# 04_-_VIDEO_INPUT.net
KiCad netlist of a schematic drawn in Altium Designer
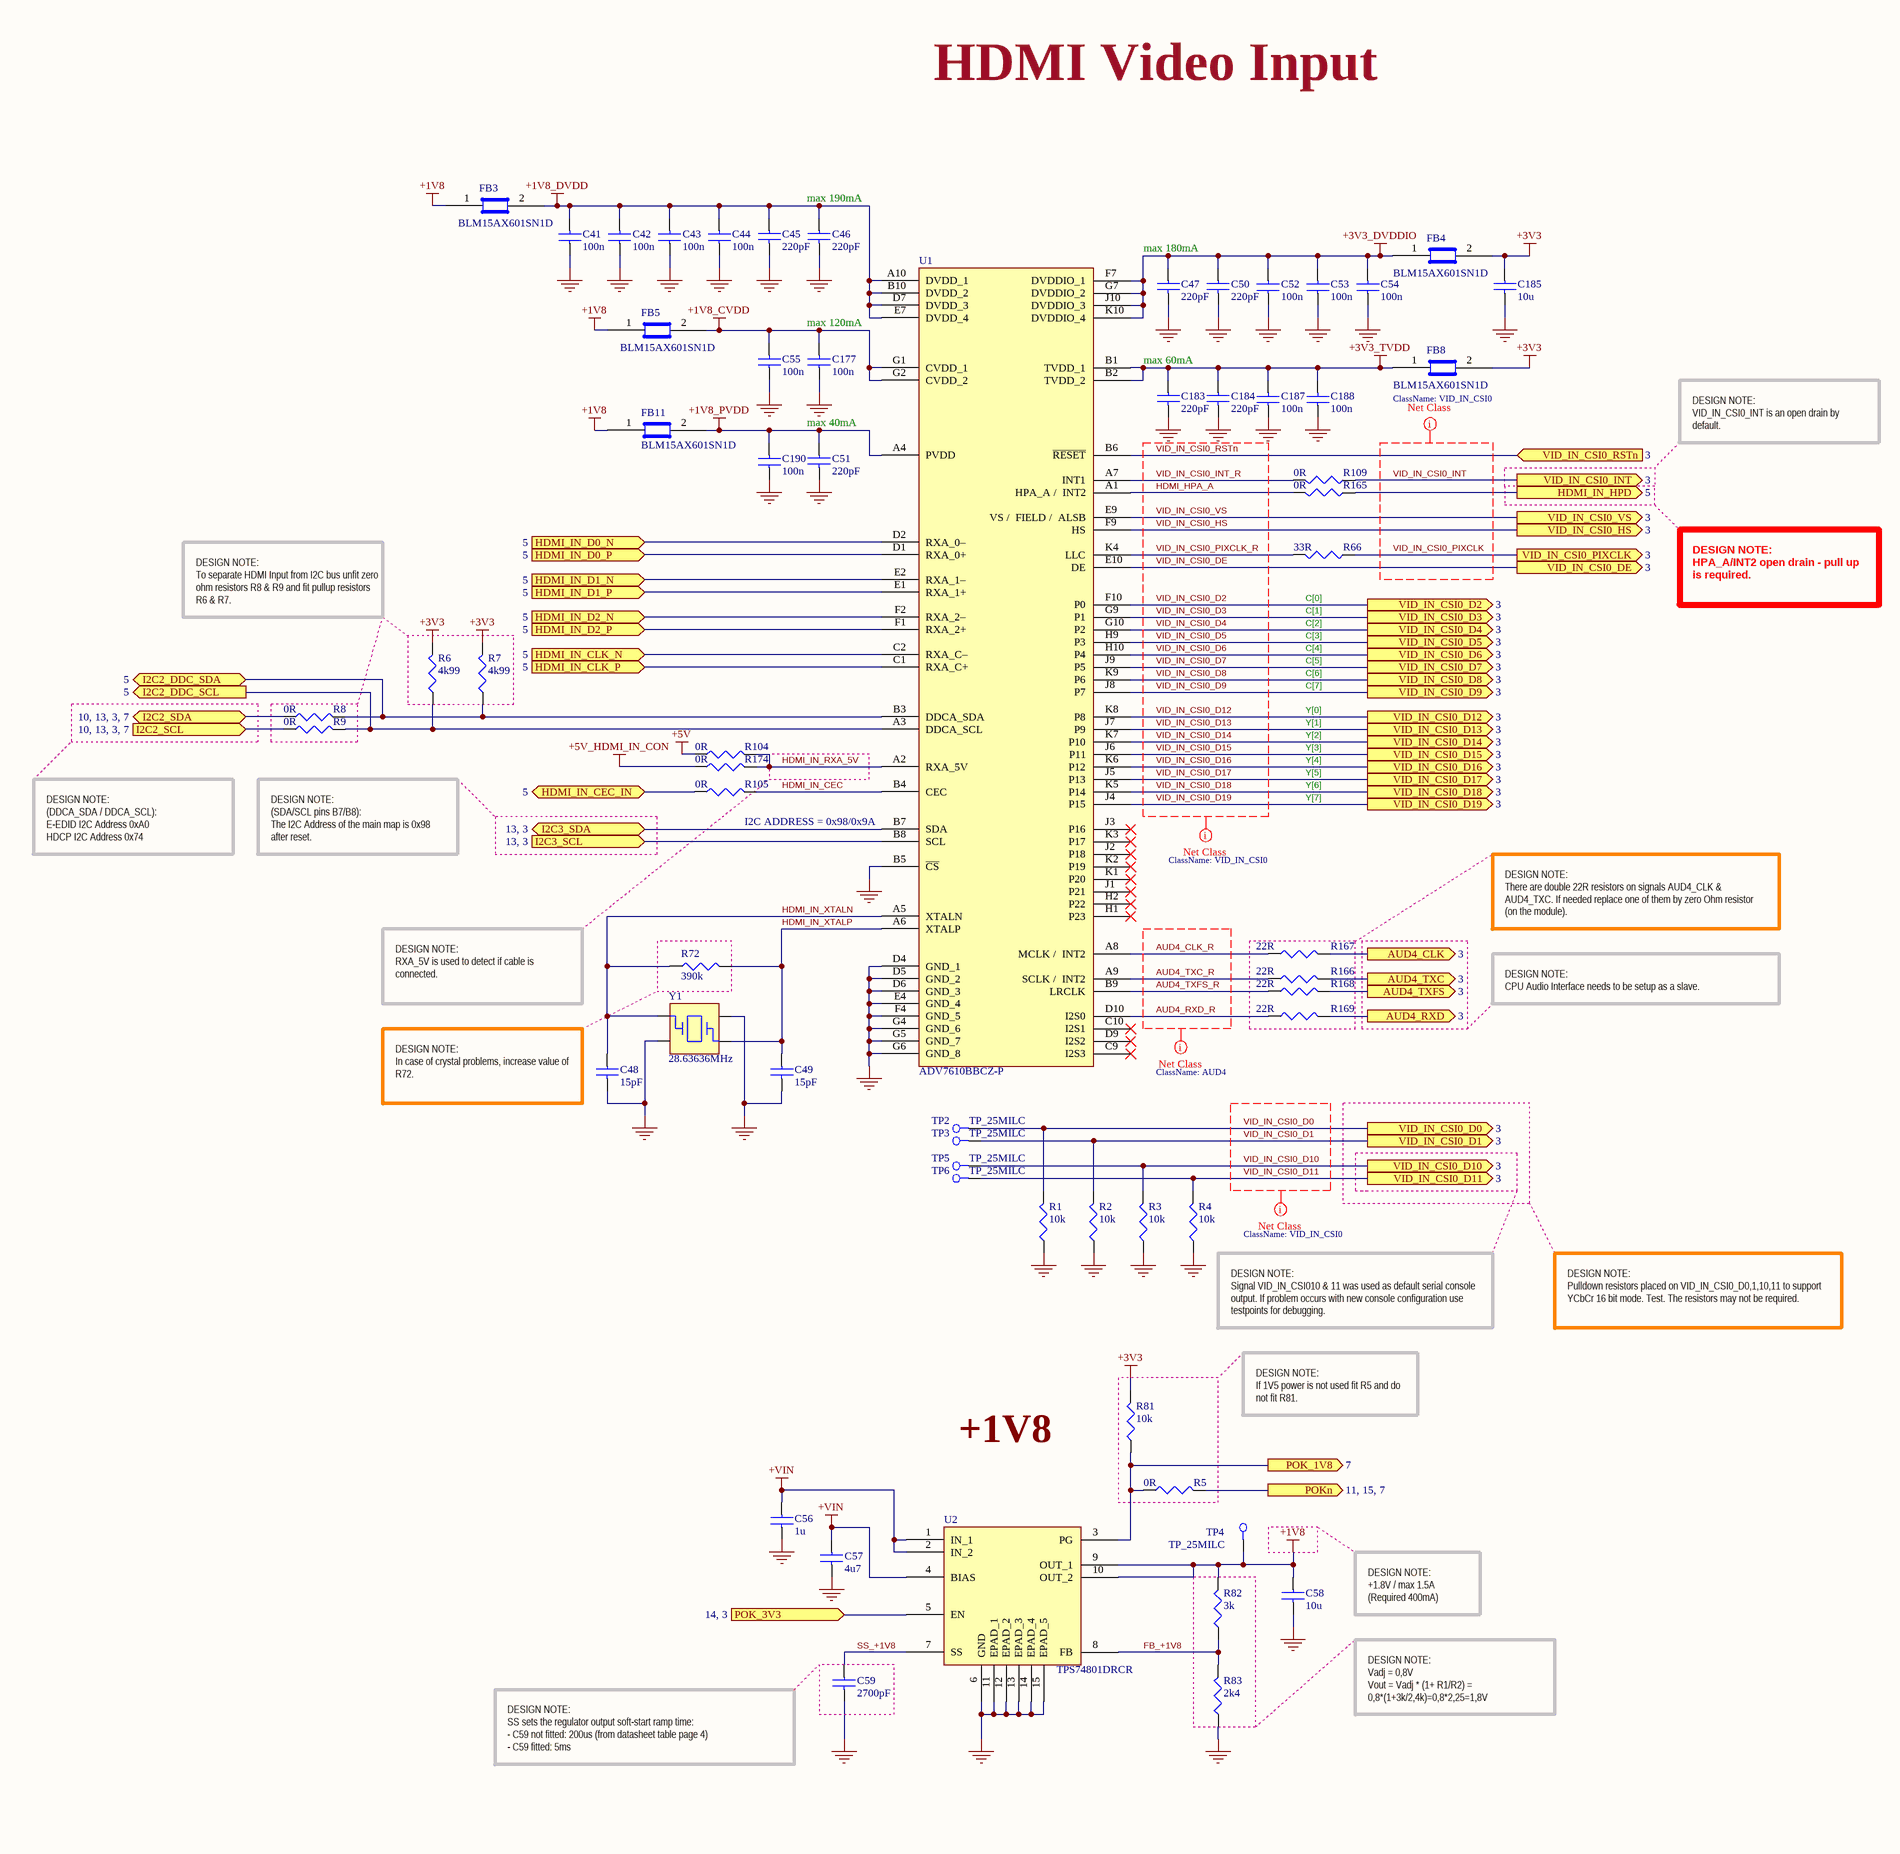
[diagram p0: [04] - VIDEO INPUT.SchDoc, left]
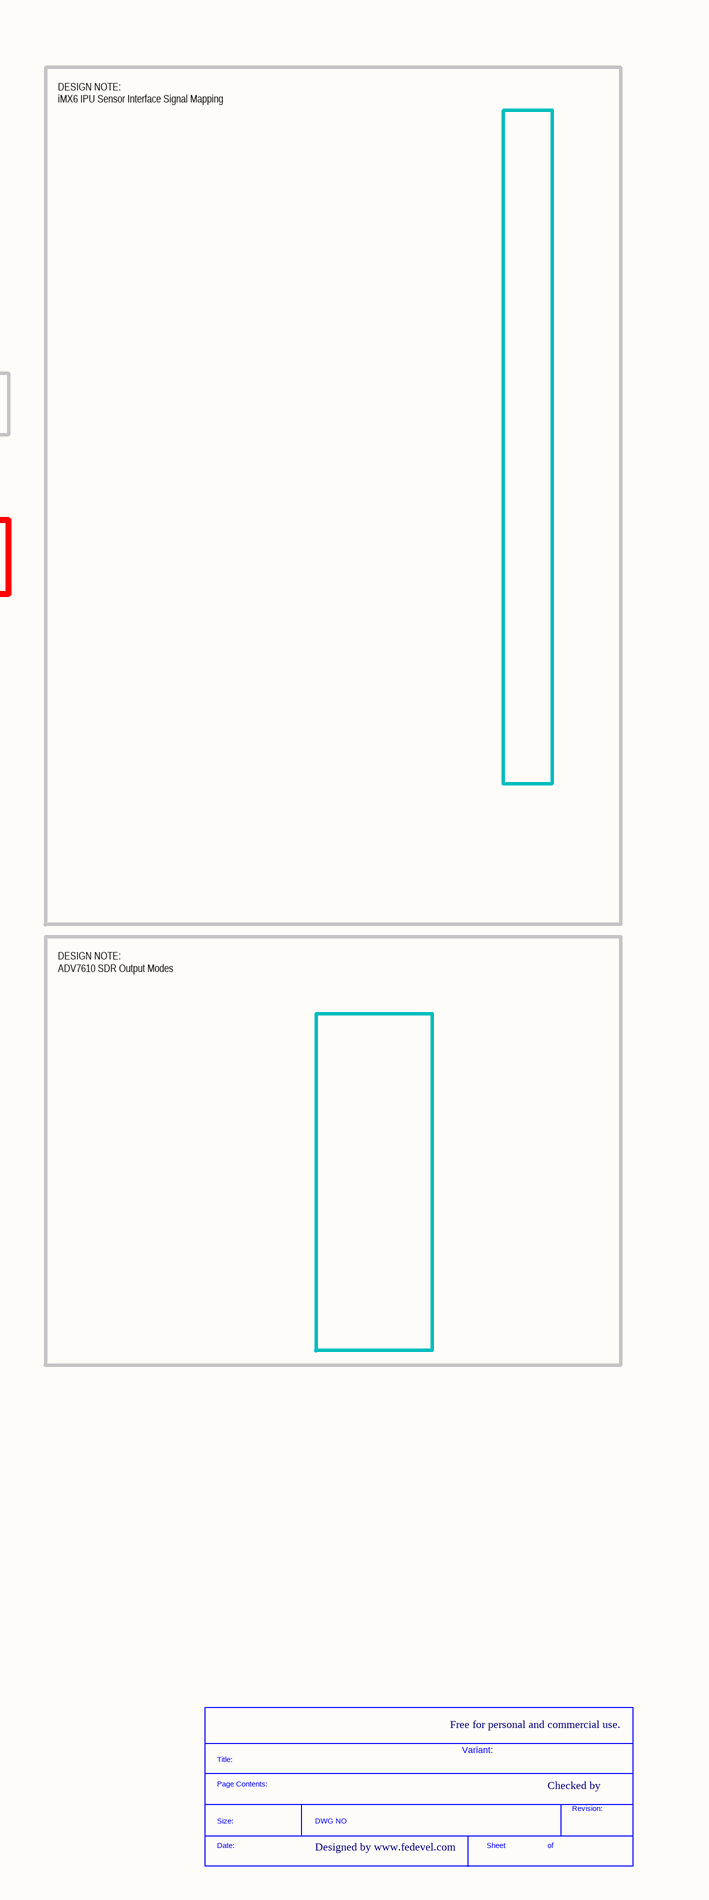
[diagram p1: [04] - VIDEO INPUT.SchDoc, right]

(export (version "E")
  (design (tool "Eeschema 10.0.6"))
  (components
    (comp (ref "C41")
      (value "100n")
      (footprint "C0402")
      (description "CAP CER .10UF 50V X5R 10% 0402")
      (fields
        (field (name "MANUFACTURER") "TDK Corporation")
        (field (name "MANUFACTURER PART NUMBER") "C1005X5R1H104K")
      )
      (libsource (lib "Integrated_Library_FEDEVEL_APR_2015") (part "C1005X5R1H104K"))
    )
    (comp (ref "C42")
      (value "100n")
      (footprint "C0402")
      (description "CAP CER .10UF 50V X5R 10% 0402")
      (fields
        (field (name "MANUFACTURER") "TDK Corporation")
        (field (name "MANUFACTURER PART NUMBER") "C1005X5R1H104K")
      )
      (libsource (lib "Integrated_Library_FEDEVEL_APR_2015") (part "C1005X5R1H104K"))
    )
    (comp (ref "C43")
      (value "100n")
      (footprint "C0402")
      (description "CAP CER .10UF 50V X5R 10% 0402")
      (fields
        (field (name "MANUFACTURER") "TDK Corporation")
        (field (name "MANUFACTURER PART NUMBER") "C1005X5R1H104K")
      )
      (libsource (lib "Integrated_Library_FEDEVEL_APR_2015") (part "C1005X5R1H104K"))
    )
    (comp (ref "C44")
      (value "100n")
      (footprint "C0402")
      (description "CAP CER .10UF 50V X5R 10% 0402")
      (fields
        (field (name "MANUFACTURER") "TDK Corporation")
        (field (name "MANUFACTURER PART NUMBER") "C1005X5R1H104K")
      )
      (libsource (lib "Integrated_Library_FEDEVEL_APR_2015") (part "C1005X5R1H104K"))
    )
    (comp (ref "C45")
      (value "220pF")
      (footprint "C0402")
      (description "CAP CER 220PF 50V X7R 10% 0402")
      (fields
        (field (name "MANUFACTURER") "TDK Corporation")
        (field (name "MANUFACTURER PART NUMBER") "C1005X7R1H221K")
      )
      (libsource (lib "Integrated_Library_FEDEVEL_APR_2015") (part "C1005X7R1H221K"))
    )
    (comp (ref "C46")
      (value "220pF")
      (footprint "C0402")
      (description "CAP CER 220PF 50V X7R 10% 0402")
      (fields
        (field (name "MANUFACTURER") "TDK Corporation")
        (field (name "MANUFACTURER PART NUMBER") "C1005X7R1H221K")
      )
      (libsource (lib "Integrated_Library_FEDEVEL_APR_2015") (part "C1005X7R1H221K"))
    )
    (comp (ref "C47")
      (value "220pF")
      (footprint "C0402")
      (description "CAP CER 220PF 50V X7R 10% 0402")
      (fields
        (field (name "MANUFACTURER") "TDK Corporation")
        (field (name "MANUFACTURER PART NUMBER") "C1005X7R1H221K")
      )
      (libsource (lib "Integrated_Library_FEDEVEL_APR_2015") (part "C1005X7R1H221K"))
    )
    (comp (ref "C48")
      (value "15pF")
      (footprint "C0402")
      (description "CAP CER 15PF 50V 5% NP0 0402")
      (fields
        (field (name "MANUFACTURER") "TDK Corporation")
        (field (name "MANUFACTURER PART NUMBER") "C1005C0G1H150J")
      )
      (libsource (lib "Integrated_Library_FEDEVEL_APR_2015") (part "C1005C0G1H150J"))
    )
    (comp (ref "C49")
      (value "15pF")
      (footprint "C0402")
      (description "CAP CER 15PF 50V 5% NP0 0402")
      (fields
        (field (name "MANUFACTURER") "TDK Corporation")
        (field (name "MANUFACTURER PART NUMBER") "C1005C0G1H150J")
      )
      (libsource (lib "Integrated_Library_FEDEVEL_APR_2015") (part "C1005C0G1H150J"))
    )
    (comp (ref "C50")
      (value "220pF")
      (footprint "C0402")
      (description "CAP CER 220PF 50V X7R 10% 0402")
      (fields
        (field (name "MANUFACTURER") "TDK Corporation")
        (field (name "MANUFACTURER PART NUMBER") "C1005X7R1H221K")
      )
      (libsource (lib "Integrated_Library_FEDEVEL_APR_2015") (part "C1005X7R1H221K"))
    )
    (comp (ref "C51")
      (value "220pF")
      (footprint "C0402")
      (description "CAP CER 220PF 50V X7R 10% 0402")
      (fields
        (field (name "MANUFACTURER") "TDK Corporation")
        (field (name "MANUFACTURER PART NUMBER") "C1005X7R1H221K")
      )
      (libsource (lib "Integrated_Library_FEDEVEL_APR_2015") (part "C1005X7R1H221K"))
    )
    (comp (ref "C52")
      (value "100n")
      (footprint "C0402")
      (description "CAP CER .10UF 50V X5R 10% 0402")
      (fields
        (field (name "MANUFACTURER") "TDK Corporation")
        (field (name "MANUFACTURER PART NUMBER") "C1005X5R1H104K")
      )
      (libsource (lib "Integrated_Library_FEDEVEL_APR_2015") (part "C1005X5R1H104K"))
    )
    (comp (ref "C53")
      (value "100n")
      (footprint "C0402")
      (description "CAP CER .10UF 50V X5R 10% 0402")
      (fields
        (field (name "MANUFACTURER") "TDK Corporation")
        (field (name "MANUFACTURER PART NUMBER") "C1005X5R1H104K")
      )
      (libsource (lib "Integrated_Library_FEDEVEL_APR_2015") (part "C1005X5R1H104K"))
    )
    (comp (ref "C54")
      (value "100n")
      (footprint "C0402")
      (description "CAP CER .10UF 50V X5R 10% 0402")
      (fields
        (field (name "MANUFACTURER") "TDK Corporation")
        (field (name "MANUFACTURER PART NUMBER") "C1005X5R1H104K")
      )
      (libsource (lib "Integrated_Library_FEDEVEL_APR_2015") (part "C1005X5R1H104K"))
    )
    (comp (ref "C55")
      (value "100n")
      (footprint "C0402")
      (description "CAP CER .10UF 50V X5R 10% 0402")
      (fields
        (field (name "MANUFACTURER") "TDK Corporation")
        (field (name "MANUFACTURER PART NUMBER") "C1005X5R1H104K")
      )
      (libsource (lib "Integrated_Library_FEDEVEL_APR_2015") (part "C1005X5R1H104K"))
    )
    (comp (ref "C56")
      (value "1u")
      (footprint "C0402")
      (description "CAP CER 1.0UF 16V X5R 0402")
      (fields
        (field (name "MANUFACTURER") "TDK Corporation")
        (field (name "MANUFACTURER PART NUMBER") "C1005X5R1C105K")
      )
      (libsource (lib "Integrated_Library_FEDEVEL_APR_2015") (part "C1005X5R1C105K"))
    )
    (comp (ref "C57")
      (value "4u7")
      (footprint "C0402")
      (description "CAP CER 4.7UF 10V 20% X5R 0402")
      (fields
        (field (name "MANUFACTURER") "TDK Corporation")
        (field (name "MANUFACTURER PART NUMBER") "C1005X5R1A475M")
      )
      (libsource (lib "Integrated_Library_FEDEVEL_APR_2015") (part "C1005X5R1A475M"))
    )
    (comp (ref "C58")
      (value "10u")
      (footprint "C0603")
      (description "CAP CER 10UF 6.3V X5R 20% 0603")
      (fields
        (field (name "MANUFACTURER") "TDK Corporation")
        (field (name "MANUFACTURER PART NUMBER") "C1608X5R0J106M")
      )
      (libsource (lib "Integrated_Library_FEDEVEL_APR_2015") (part "C1608X5R0J106M"))
    )
    (comp (ref "C59")
      (value "2700pF")
      (footprint "C0402")
      (description "CAP CER 2700PF 50V 10% X7R 0402")
      (fields
        (field (name "MANUFACTURER") "Murata Electronics North America")
        (field (name "MANUFACTURER PART NUMBER") "GRM155R71H272KA01D")
      )
      (libsource (lib "Integrated_Library_FEDEVEL_APR_2015") (part "GRM155R71H272KA01D"))
    )
    (comp (ref "C177")
      (value "100n")
      (footprint "C0402")
      (description "CAP CER .10UF 50V X5R 10% 0402")
      (fields
        (field (name "MANUFACTURER") "TDK Corporation")
        (field (name "MANUFACTURER PART NUMBER") "C1005X5R1H104K")
      )
      (libsource (lib "Integrated_Library_FEDEVEL_APR_2015") (part "C1005X5R1H104K"))
    )
    (comp (ref "C183")
      (value "220pF")
      (footprint "C0402")
      (description "CAP CER 220PF 50V X7R 10% 0402")
      (fields
        (field (name "MANUFACTURER") "TDK Corporation")
        (field (name "MANUFACTURER PART NUMBER") "C1005X7R1H221K")
      )
      (libsource (lib "Integrated_Library_FEDEVEL_APR_2015") (part "C1005X7R1H221K"))
    )
    (comp (ref "C184")
      (value "220pF")
      (footprint "C0402")
      (description "CAP CER 220PF 50V X7R 10% 0402")
      (fields
        (field (name "MANUFACTURER") "TDK Corporation")
        (field (name "MANUFACTURER PART NUMBER") "C1005X7R1H221K")
      )
      (libsource (lib "Integrated_Library_FEDEVEL_APR_2015") (part "C1005X7R1H221K"))
    )
    (comp (ref "C185")
      (value "10u")
      (footprint "C0603")
      (description "CAP CER 10UF 6.3V X5R 20% 0603")
      (fields
        (field (name "MANUFACTURER") "TDK Corporation")
        (field (name "MANUFACTURER PART NUMBER") "C1608X5R0J106M")
      )
      (libsource (lib "Integrated_Library_FEDEVEL_APR_2015") (part "C1608X5R0J106M"))
    )
    (comp (ref "C187")
      (value "100n")
      (footprint "C0402")
      (description "CAP CER .10UF 50V X5R 10% 0402")
      (fields
        (field (name "MANUFACTURER") "TDK Corporation")
        (field (name "MANUFACTURER PART NUMBER") "C1005X5R1H104K")
      )
      (libsource (lib "Integrated_Library_FEDEVEL_APR_2015") (part "C1005X5R1H104K"))
    )
    (comp (ref "C188")
      (value "100n")
      (footprint "C0402")
      (description "CAP CER .10UF 50V X5R 10% 0402")
      (fields
        (field (name "MANUFACTURER") "TDK Corporation")
        (field (name "MANUFACTURER PART NUMBER") "C1005X5R1H104K")
      )
      (libsource (lib "Integrated_Library_FEDEVEL_APR_2015") (part "C1005X5R1H104K"))
    )
    (comp (ref "C190")
      (value "100n")
      (footprint "C0402")
      (description "CAP CER .10UF 50V X5R 10% 0402")
      (fields
        (field (name "MANUFACTURER") "TDK Corporation")
        (field (name "MANUFACTURER PART NUMBER") "C1005X5R1H104K")
      )
      (libsource (lib "Integrated_Library_FEDEVEL_APR_2015") (part "C1005X5R1H104K"))
    )
    (comp (ref "FB3")
      (value "BLM15AX601SN1D")
      (footprint "C0402")
      (description "FERRITE CHIP 600 OHM 0402 420mA")
      (fields (field (name "MANUFACTURER") "Murata Electronics North America"))
      (libsource (lib "Integrated_Library_FEDEVEL_APR_2015") (part "BLM15AX601SN1D"))
    )
    (comp (ref "FB4")
      (value "BLM15AX601SN1D")
      (footprint "C0402")
      (description "FERRITE CHIP 600 OHM 0402 420mA")
      (fields (field (name "MANUFACTURER") "Murata Electronics North America"))
      (libsource (lib "Integrated_Library_FEDEVEL_APR_2015") (part "BLM15AX601SN1D"))
    )
    (comp (ref "FB5")
      (value "BLM15AX601SN1D")
      (footprint "C0402")
      (description "FERRITE CHIP 600 OHM 0402 420mA")
      (fields (field (name "MANUFACTURER") "Murata Electronics North America"))
      (libsource (lib "Integrated_Library_FEDEVEL_APR_2015") (part "BLM15AX601SN1D"))
    )
    (comp (ref "FB8")
      (value "BLM15AX601SN1D")
      (footprint "C0402")
      (description "FERRITE CHIP 600 OHM 0402 420mA")
      (fields (field (name "MANUFACTURER") "Murata Electronics North America"))
      (libsource (lib "Integrated_Library_FEDEVEL_APR_2015") (part "BLM15AX601SN1D"))
    )
    (comp (ref "FB11")
      (value "BLM15AX601SN1D")
      (footprint "C0402")
      (description "FERRITE CHIP 600 OHM 0402 420mA")
      (fields (field (name "MANUFACTURER") "Murata Electronics North America"))
      (libsource (lib "Integrated_Library_FEDEVEL_APR_2015") (part "BLM15AX601SN1D"))
    )
    (comp (ref "R1")
      (value "10k")
      (footprint "R0402")
      (description "RES 10.0K OHM 1/16W 1% 0402 SMD")
      (fields
        (field (name "MANUFACTURER") "Yageo")
        (field (name "MANUFACTURER PART NUMBER") "RC0402FR-0710KL")
      )
      (libsource (lib "Integrated_Library_FEDEVEL_APR_2015") (part "RC0402FR-0710KL"))
    )
    (comp (ref "R2")
      (value "10k")
      (footprint "R0402")
      (description "RES 10.0K OHM 1/16W 1% 0402 SMD")
      (fields
        (field (name "MANUFACTURER") "Yageo")
        (field (name "MANUFACTURER PART NUMBER") "RC0402FR-0710KL")
      )
      (libsource (lib "Integrated_Library_FEDEVEL_APR_2015") (part "RC0402FR-0710KL"))
    )
    (comp (ref "R3")
      (value "10k")
      (footprint "R0402")
      (description "RES 10.0K OHM 1/16W 1% 0402 SMD")
      (fields
        (field (name "MANUFACTURER") "Yageo")
        (field (name "MANUFACTURER PART NUMBER") "RC0402FR-0710KL")
      )
      (libsource (lib "Integrated_Library_FEDEVEL_APR_2015") (part "RC0402FR-0710KL"))
    )
    (comp (ref "R4")
      (value "10k")
      (footprint "R0402")
      (description "RES 10.0K OHM 1/16W 1% 0402 SMD")
      (fields
        (field (name "MANUFACTURER") "Yageo")
        (field (name "MANUFACTURER PART NUMBER") "RC0402FR-0710KL")
      )
      (libsource (lib "Integrated_Library_FEDEVEL_APR_2015") (part "RC0402FR-0710KL"))
    )
    (comp (ref "R5")
      (value "0R")
      (footprint "R0402")
      (description "RES 0.0 OHM 1/16W 0402 SMD")
      (fields
        (field (name "MANUFACTURER") "Yageo")
        (field (name "MANUFACTURER PART NUMBER") "RC0402JR-070RL")
      )
      (libsource (lib "Integrated_Library_FEDEVEL_APR_2015") (part "RC0402JR-070RL"))
    )
    (comp (ref "R6")
      (value "4k99")
      (footprint "R0402")
      (description "RES TF 4.99K OHM 1% 1/16W 0402")
      (fields
        (field (name "MANUFACTURER") "Stackpole Electronics Inc")
        (field (name "MANUFACTURER PART NUMBER") "RMCF0402FT4K99")
      )
      (libsource (lib "Integrated_Library_FEDEVEL_APR_2015") (part "RMCF0402FT4K99"))
    )
    (comp (ref "R7")
      (value "4k99")
      (footprint "R0402")
      (description "RES TF 4.99K OHM 1% 1/16W 0402")
      (fields
        (field (name "MANUFACTURER") "Stackpole Electronics Inc")
        (field (name "MANUFACTURER PART NUMBER") "RMCF0402FT4K99")
      )
      (libsource (lib "Integrated_Library_FEDEVEL_APR_2015") (part "RMCF0402FT4K99"))
    )
    (comp (ref "R8")
      (value "0R")
      (footprint "R0402")
      (description "RES 0.0 OHM 1/16W 0402 SMD")
      (fields
        (field (name "MANUFACTURER") "Yageo")
        (field (name "MANUFACTURER PART NUMBER") "RC0402JR-070RL")
      )
      (libsource (lib "Integrated_Library_FEDEVEL_APR_2015") (part "RC0402JR-070RL"))
    )
    (comp (ref "R9")
      (value "0R")
      (footprint "R0402")
      (description "RES 0.0 OHM 1/16W 0402 SMD")
      (fields
        (field (name "MANUFACTURER") "Yageo")
        (field (name "MANUFACTURER PART NUMBER") "RC0402JR-070RL")
      )
      (libsource (lib "Integrated_Library_FEDEVEL_APR_2015") (part "RC0402JR-070RL"))
    )
    (comp (ref "R66")
      (value "33R")
      (footprint "R0402")
      (description "RES TF 33 OHM 1% 1/16W 0402")
      (fields
        (field (name "MANUFACTURER") "Stackpole Electronics Inc")
        (field (name "MANUFACTURER PART NUMBER") "RMCF0402FT33R0")
      )
      (libsource (lib "Integrated_Library_FEDEVEL_APR_2015") (part "RMCF0402FT33R0"))
    )
    (comp (ref "R72")
      (value "390k")
      (footprint "R0402")
      (description "RES 390K OHM 1/16W 1% 0402 SMD")
      (fields
        (field (name "MANUFACTURER") "Vishay Dale")
        (field (name "MANUFACTURER PART NUMBER") "CRCW0402390KFKED")
        (field (name ".CREATOR") "MM")
      )
      (libsource (lib "Integrated_Library_FEDEVEL_APR_2015") (part "CRCW0402390KFKED"))
    )
    (comp (ref "R81")
      (value "10k")
      (footprint "R0402")
      (description "RES 10.0K OHM 1/16W 1% 0402 SMD")
      (fields
        (field (name "MANUFACTURER") "Yageo")
        (field (name "MANUFACTURER PART NUMBER") "RC0402FR-0710KL")
      )
      (libsource (lib "Integrated_Library_FEDEVEL_APR_2015") (part "RC0402FR-0710KL"))
    )
    (comp (ref "R82")
      (value "3k")
      (footprint "R0402")
      (description "RES 3K OHM 1/16W 1% 0402 SMD")
      (fields
        (field (name "MANUFACTURER") "Yageo")
        (field (name "MANUFACTURER PART NUMBER") "RC0402FR-073KL")
        (field (name ".CREATOR") "MM")
      )
      (libsource (lib "Integrated_Library_FEDEVEL_APR_2015") (part "RC0402FR-073KL"))
    )
    (comp (ref "R83")
      (value "2k4")
      (footprint "R0402")
      (description "RES 2.40K OHM 1/16W 1% 0402 SMD")
      (fields
        (field (name "MANUFACTURER") "Vishay Dale")
        (field (name "MANUFACTURER PART NUMBER") "CRCW04022K40FKED")
      )
      (libsource (lib "Integrated_Library_FEDEVEL_APR_2015") (part "CRCW04022K40FKED"))
    )
    (comp (ref "R104")
      (value "0R")
      (footprint "R0402")
      (description "RES 0.0 OHM 1/16W 0402 SMD")
      (fields
        (field (name "MANUFACTURER") "Yageo")
        (field (name "MANUFACTURER PART NUMBER") "RC0402JR-070RL")
      )
      (libsource (lib "Integrated_Library_FEDEVEL_APR_2015") (part "RC0402JR-070RL"))
    )
    (comp (ref "R105")
      (value "0R")
      (footprint "R0402")
      (description "RES 0.0 OHM 1/16W 0402 SMD")
      (fields
        (field (name "MANUFACTURER") "Yageo")
        (field (name "MANUFACTURER PART NUMBER") "RC0402JR-070RL")
      )
      (libsource (lib "Integrated_Library_FEDEVEL_APR_2015") (part "RC0402JR-070RL"))
    )
    (comp (ref "R109")
      (value "0R")
      (footprint "R0402")
      (description "RES 0.0 OHM 1/16W 0402 SMD")
      (fields
        (field (name "MANUFACTURER") "Yageo")
        (field (name "MANUFACTURER PART NUMBER") "RC0402JR-070RL")
      )
      (libsource (lib "Integrated_Library_FEDEVEL_APR_2015") (part "RC0402JR-070RL"))
    )
    (comp (ref "R165")
      (value "0R")
      (footprint "R0402")
      (description "RES 0.0 OHM 1/16W 0402 SMD")
      (fields
        (field (name "MANUFACTURER") "Yageo")
        (field (name "MANUFACTURER PART NUMBER") "RC0402JR-070RL")
      )
      (libsource (lib "Integrated_Library_FEDEVEL_APR_2015") (part "RC0402JR-070RL"))
    )
    (comp (ref "R166")
      (value "22R")
      (footprint "R0402")
      (description "RES 22.0 OHM 1/16W 1% 0402 SMD")
      (fields
        (field (name "MANUFACTURER") "Yageo")
        (field (name "MANUFACTURER PART NUMBER") "RC0402FR-0722RL")
      )
      (libsource (lib "Integrated_Library_FEDEVEL_APR_2015") (part "RC0402FR-0722RL"))
    )
    (comp (ref "R167")
      (value "22R")
      (footprint "R0402")
      (description "RES 22.0 OHM 1/16W 1% 0402 SMD")
      (fields
        (field (name "MANUFACTURER") "Yageo")
        (field (name "MANUFACTURER PART NUMBER") "RC0402FR-0722RL")
      )
      (libsource (lib "Integrated_Library_FEDEVEL_APR_2015") (part "RC0402FR-0722RL"))
    )
    (comp (ref "R168")
      (value "22R")
      (footprint "R0402")
      (description "RES 22.0 OHM 1/16W 1% 0402 SMD")
      (fields
        (field (name "MANUFACTURER") "Yageo")
        (field (name "MANUFACTURER PART NUMBER") "RC0402FR-0722RL")
      )
      (libsource (lib "Integrated_Library_FEDEVEL_APR_2015") (part "RC0402FR-0722RL"))
    )
    (comp (ref "R169")
      (value "22R")
      (footprint "R0402")
      (description "RES 22.0 OHM 1/16W 1% 0402 SMD")
      (fields
        (field (name "MANUFACTURER") "Yageo")
        (field (name "MANUFACTURER PART NUMBER") "RC0402FR-0722RL")
      )
      (libsource (lib "Integrated_Library_FEDEVEL_APR_2015") (part "RC0402FR-0722RL"))
    )
    (comp (ref "R174")
      (value "0R")
      (footprint "R0402")
      (description "RES 0.0 OHM 1/16W 0402 SMD")
      (fields
        (field (name "MANUFACTURER") "Yageo")
        (field (name "MANUFACTURER PART NUMBER") "RC0402JR-070RL")
      )
      (libsource (lib "Integrated_Library_FEDEVEL_APR_2015") (part "RC0402JR-070RL"))
    )
    (comp (ref "TP2")
      (value "TP_25MILC")
      (footprint "TP_25C")
      (description "Test Point 25mil")
      (libsource (lib "Integrated_Library_FEDEVEL_APR_2015") (part "TP_25MILC"))
    )
    (comp (ref "TP3")
      (value "TP_25MILC")
      (footprint "TP_25C")
      (description "Test Point 25mil")
      (libsource (lib "Integrated_Library_FEDEVEL_APR_2015") (part "TP_25MILC"))
    )
    (comp (ref "TP4")
      (value "TP_25MILC")
      (footprint "TP_25C")
      (description "Test Point 25mil")
      (libsource (lib "Integrated_Library_FEDEVEL_APR_2015") (part "TP_25MILC"))
    )
    (comp (ref "TP5")
      (value "TP_25MILC")
      (footprint "TP_25C")
      (description "Test Point 25mil")
      (libsource (lib "Integrated_Library_FEDEVEL_APR_2015") (part "TP_25MILC"))
    )
    (comp (ref "TP6")
      (value "TP_25MILC")
      (footprint "TP_25C")
      (description "Test Point 25mil")
      (libsource (lib "Integrated_Library_FEDEVEL_APR_2015") (part "TP_25MILC"))
    )
    (comp (ref "U1")
      (value "ADV7610BBCZ-P")
      (footprint "76_CSP_BGA")
      (description "IC RCVR HDMI 165MHZ LP 76-CSBGA")
      (fields (field (name "MANUFACTURER") "Analog Devices Inc") (field (name ".CREATOR") "MM"))
      (libsource (lib "Integrated_Library_FEDEVEL_APR_2015") (part "ADV7610BBCZ-P"))
    )
    (comp (ref "U2")
      (value "TPS74801DRCR")
      (footprint "DRC (S-PVSON-N10)")
      (description "IC REG LDO ADJ 1.5A 10SON")
      (fields (field (name "MANUFACTURER") "Texas Instruments") (field (name ".CREATOR") "MM"))
      (libsource (lib "Integrated_Library_FEDEVEL_APR_2015") (part "TPS74801DRCR"))
    )
    (comp (ref "Y1")
      (value "28.63636MHz")
      (footprint "ABM3B")
      (description "CRYSTAL 28.63636MHZ 10PF SMD")
      (fields
        (field (name "MANUFACTURER") "Abracon Corporation")
        (field (name "MANUFACTURER PART NUMBER") "ABM3B-28.63636MHZ-10-1-U-T")
        (field (name ".CREATOR") "MM")
        (field (name ".CHECKED PCB") "MM, paper model not checked")
        (field (name ".CHECKED SCH") "MM")
      )
      (libsource (lib "Integrated_Library_FEDEVEL_APR_2015") (part "ABM3B-28.63636MHZ-10-1-U-T"))
    )
  )
  (nets
    (net (code "1") (name "+1V8") (class "Default")
      (node (ref "C58") (pin "1") (pinfunction "1_1") (pintype "passive"))
      (node (ref "FB11") (pin "1") (pinfunction "1_1") (pintype "passive"))
      (node (ref "FB3") (pin "1") (pinfunction "1_1") (pintype "passive"))
      (node (ref "FB5") (pin "1") (pinfunction "1_1") (pintype "passive"))
      (node (ref "R82") (pin "2") (pinfunction "2_2") (pintype "passive"))
      (node (ref "TP4") (pin "1") (pinfunction "1_1") (pintype "passive"))
      (node (ref "U2") (pin "10") (pinfunction "OUT_2_10") (pintype "passive"))
      (node (ref "U2") (pin "9") (pinfunction "OUT_1_9") (pintype "passive"))
    )
    (net (code "2") (name "+1V8_CVDD") (class "Default")
      (node (ref "C177") (pin "2") (pinfunction "2_2") (pintype "passive"))
      (node (ref "C55") (pin "2") (pinfunction "2_2") (pintype "passive"))
      (node (ref "FB5") (pin "2") (pinfunction "2_2") (pintype "passive"))
      (node (ref "U1") (pin "G1") (pinfunction "CVDD_1_G1") (pintype "passive"))
      (node (ref "U1") (pin "G2") (pinfunction "CVDD_2_G2") (pintype "passive"))
    )
    (net (code "3") (name "+1V8_DVDD") (class "Default")
      (node (ref "C41") (pin "2") (pinfunction "2_2") (pintype "passive"))
      (node (ref "C42") (pin "2") (pinfunction "2_2") (pintype "passive"))
      (node (ref "C43") (pin "2") (pinfunction "2_2") (pintype "passive"))
      (node (ref "C44") (pin "2") (pinfunction "2_2") (pintype "passive"))
      (node (ref "C45") (pin "1") (pinfunction "1_1") (pintype "passive"))
      (node (ref "C46") (pin "1") (pinfunction "1_1") (pintype "passive"))
      (node (ref "FB3") (pin "2") (pinfunction "2_2") (pintype "passive"))
      (node (ref "U1") (pin "A10") (pinfunction "DVDD_1_A10") (pintype "passive"))
      (node (ref "U1") (pin "B10") (pinfunction "DVDD_2_B10") (pintype "passive"))
      (node (ref "U1") (pin "D7") (pinfunction "DVDD_3_D7") (pintype "passive"))
      (node (ref "U1") (pin "E7") (pinfunction "DVDD_4_E7") (pintype "passive"))
    )
    (net (code "4") (name "+1V8_PVDD") (class "Default")
      (node (ref "C190") (pin "2") (pinfunction "2_2") (pintype "passive"))
      (node (ref "C51") (pin "1") (pinfunction "1_1") (pintype "passive"))
      (node (ref "FB11") (pin "2") (pinfunction "2_2") (pintype "passive"))
      (node (ref "U1") (pin "A4") (pinfunction "PVDD_A4") (pintype "passive"))
    )
    (net (code "5") (name "+3V3") (class "Default")
      (node (ref "C185") (pin "1") (pinfunction "1_1") (pintype "passive"))
      (node (ref "FB4") (pin "2") (pinfunction "2_2") (pintype "passive"))
      (node (ref "FB8") (pin "2") (pinfunction "2_2") (pintype "passive"))
      (node (ref "R6") (pin "2") (pinfunction "2_2") (pintype "passive"))
      (node (ref "R7") (pin "2") (pinfunction "2_2") (pintype "passive"))
      (node (ref "R81") (pin "2") (pinfunction "2_2") (pintype "passive"))
    )
    (net (code "6") (name "+3V3_DVDDIO") (class "Default")
      (node (ref "C47") (pin "1") (pinfunction "1_1") (pintype "passive"))
      (node (ref "C50") (pin "1") (pinfunction "1_1") (pintype "passive"))
      (node (ref "C52") (pin "2") (pinfunction "2_2") (pintype "passive"))
      (node (ref "C53") (pin "2") (pinfunction "2_2") (pintype "passive"))
      (node (ref "C54") (pin "2") (pinfunction "2_2") (pintype "passive"))
      (node (ref "FB4") (pin "1") (pinfunction "1_1") (pintype "passive"))
      (node (ref "U1") (pin "F7") (pinfunction "DVDDIO_1_F7") (pintype "passive"))
      (node (ref "U1") (pin "G7") (pinfunction "DVDDIO_2_G7") (pintype "passive"))
      (node (ref "U1") (pin "J10") (pinfunction "DVDDIO_3_J10") (pintype "passive"))
      (node (ref "U1") (pin "K10") (pinfunction "DVDDIO_4_K10") (pintype "passive"))
    )
    (net (code "7") (name "+3V3_TVDD") (class "Default")
      (node (ref "C183") (pin "1") (pinfunction "1_1") (pintype "passive"))
      (node (ref "C184") (pin "1") (pinfunction "1_1") (pintype "passive"))
      (node (ref "C187") (pin "2") (pinfunction "2_2") (pintype "passive"))
      (node (ref "C188") (pin "2") (pinfunction "2_2") (pintype "passive"))
      (node (ref "FB8") (pin "1") (pinfunction "1_1") (pintype "passive"))
      (node (ref "U1") (pin "B1") (pinfunction "TVDD_1_B1") (pintype "passive"))
      (node (ref "U1") (pin "B2") (pinfunction "TVDD_2_B2") (pintype "passive"))
    )
    (net (code "8") (name "+5V") (class "Default")
      (node (ref "R104") (pin "1") (pinfunction "1_1") (pintype "passive"))
    )
    (net (code "9") (name "+5V_HDMI_IN_CON") (class "Default")
      (node (ref "R174") (pin "1") (pinfunction "1_1") (pintype "passive"))
    )
    (net (code "10") (name "+VIN") (class "Default")
      (node (ref "C56") (pin "1") (pinfunction "1_1") (pintype "passive"))
      (node (ref "C57") (pin "1") (pinfunction "1_1") (pintype "passive"))
      (node (ref "U2") (pin "1") (pinfunction "IN_1_1") (pintype "passive"))
      (node (ref "U2") (pin "2") (pinfunction "IN_2_2") (pintype "passive"))
      (node (ref "U2") (pin "4") (pinfunction "BIAS_4") (pintype "passive"))
    )
    (net (code "11") (name "/AUD4_CLK") (class "Default")
      (node (ref "R167") (pin "2") (pinfunction "2_2") (pintype "passive"))
    )
    (net (code "12") (name "/AUD4_CLK_R") (class "Default")
      (node (ref "R167") (pin "1") (pinfunction "1_1") (pintype "passive"))
      (node (ref "U1") (pin "A8") (pinfunction "MCLK_/__INT2_A8") (pintype "passive"))
    )
    (net (code "13") (name "/AUD4_RXD") (class "Default")
      (node (ref "R169") (pin "2") (pinfunction "2_2") (pintype "passive"))
    )
    (net (code "14") (name "/AUD4_RXD_R") (class "Default")
      (node (ref "R169") (pin "1") (pinfunction "1_1") (pintype "passive"))
      (node (ref "U1") (pin "D10") (pinfunction "I2S0_D10") (pintype "passive"))
    )
    (net (code "15") (name "/AUD4_TXC") (class "Default")
      (node (ref "R166") (pin "2") (pinfunction "2_2") (pintype "passive"))
    )
    (net (code "16") (name "/AUD4_TXC_R") (class "Default")
      (node (ref "R166") (pin "1") (pinfunction "1_1") (pintype "passive"))
      (node (ref "U1") (pin "A9") (pinfunction "SCLK_/__INT2_A9") (pintype "passive"))
    )
    (net (code "17") (name "/AUD4_TXFS") (class "Default")
      (node (ref "R168") (pin "2") (pinfunction "2_2") (pintype "passive"))
    )
    (net (code "18") (name "/AUD4_TXFS_R") (class "Default")
      (node (ref "R168") (pin "1") (pinfunction "1_1") (pintype "passive"))
      (node (ref "U1") (pin "B9") (pinfunction "LRCLK_B9") (pintype "passive"))
    )
    (net (code "19") (name "/FB_+1V8") (class "Default")
      (node (ref "R82") (pin "1") (pinfunction "1_1") (pintype "passive"))
      (node (ref "R83") (pin "2") (pinfunction "2_2") (pintype "passive"))
      (node (ref "U2") (pin "8") (pinfunction "FB_8") (pintype "passive"))
    )
    (net (code "20") (name "/HDMI_HPA_A") (class "Default")
      (node (ref "R165") (pin "2") (pinfunction "2_2") (pintype "passive"))
      (node (ref "U1") (pin "A1") (pinfunction "HPA_A_/__INT2_A1") (pintype "passive"))
    )
    (net (code "21") (name "/HDMI_IN_CEC") (class "Default")
      (node (ref "R105") (pin "2") (pinfunction "2_2") (pintype "passive"))
      (node (ref "U1") (pin "B4") (pinfunction "CEC_B4") (pintype "passive"))
    )
    (net (code "22") (name "/HDMI_IN_CEC_IN") (class "Default")
      (node (ref "R105") (pin "1") (pinfunction "1_1") (pintype "passive"))
    )
    (net (code "23") (name "/HDMI_IN_CLK_N") (class "Default")
      (node (ref "U1") (pin "C2") (pinfunction "RXA_C–_C2") (pintype "passive"))
    )
    (net (code "24") (name "/HDMI_IN_CLK_P") (class "Default")
      (node (ref "U1") (pin "C1") (pinfunction "RXA_C+_C1") (pintype "passive"))
    )
    (net (code "25") (name "/HDMI_IN_D0_N") (class "Default")
      (node (ref "U1") (pin "D2") (pinfunction "RXA_0–_D2") (pintype "passive"))
    )
    (net (code "26") (name "/HDMI_IN_D0_P") (class "Default")
      (node (ref "U1") (pin "D1") (pinfunction "RXA_0+_D1") (pintype "passive"))
    )
    (net (code "27") (name "/HDMI_IN_D1_N") (class "Default")
      (node (ref "U1") (pin "E2") (pinfunction "RXA_1–_E2") (pintype "passive"))
    )
    (net (code "28") (name "/HDMI_IN_D1_P") (class "Default")
      (node (ref "U1") (pin "E1") (pinfunction "RXA_1+_E1") (pintype "passive"))
    )
    (net (code "29") (name "/HDMI_IN_D2_N") (class "Default")
      (node (ref "U1") (pin "F2") (pinfunction "RXA_2–_F2") (pintype "passive"))
    )
    (net (code "30") (name "/HDMI_IN_D2_P") (class "Default")
      (node (ref "U1") (pin "F1") (pinfunction "RXA_2+_F1") (pintype "passive"))
    )
    (net (code "31") (name "/HDMI_IN_HPD") (class "Default")
      (node (ref "R165") (pin "1") (pinfunction "1_1") (pintype "passive"))
    )
    (net (code "32") (name "/HDMI_IN_RXA_5V") (class "Default")
      (node (ref "R104") (pin "2") (pinfunction "2_2") (pintype "passive"))
      (node (ref "R174") (pin "2") (pinfunction "2_2") (pintype "passive"))
      (node (ref "U1") (pin "A2") (pinfunction "RXA_5V_A2") (pintype "passive"))
    )
    (net (code "33") (name "/HDMI_IN_XTALN") (class "Default")
      (node (ref "C48") (pin "1") (pinfunction "1_1") (pintype "passive"))
      (node (ref "R72") (pin "1") (pinfunction "1_1") (pintype "passive"))
      (node (ref "U1") (pin "A5") (pinfunction "XTALN_A5") (pintype "passive"))
      (node (ref "Y1") (pin "1") (pinfunction "1_1") (pintype "passive"))
    )
    (net (code "34") (name "/HDMI_IN_XTALP") (class "Default")
      (node (ref "C49") (pin "1") (pinfunction "1_1") (pintype "passive"))
      (node (ref "R72") (pin "2") (pinfunction "2_2") (pintype "passive"))
      (node (ref "U1") (pin "A6") (pinfunction "XTALP_A6") (pintype "passive"))
      (node (ref "Y1") (pin "3") (pinfunction "3_3") (pintype "passive"))
    )
    (net (code "35") (name "/I2C2_DDC_SCL") (class "Default")
      (node (ref "R6") (pin "1") (pinfunction "1_1") (pintype "passive"))
      (node (ref "R9") (pin "2") (pinfunction "2_2") (pintype "passive"))
      (node (ref "U1") (pin "A3") (pinfunction "DDCA_SCL_A3") (pintype "passive"))
    )
    (net (code "36") (name "/I2C2_DDC_SDA") (class "Default")
      (node (ref "R7") (pin "1") (pinfunction "1_1") (pintype "passive"))
      (node (ref "R8") (pin "2") (pinfunction "2_2") (pintype "passive"))
      (node (ref "U1") (pin "B3") (pinfunction "DDCA_SDA_B3") (pintype "passive"))
    )
    (net (code "37") (name "/I2C2_SCL") (class "Default")
      (node (ref "R9") (pin "1") (pinfunction "1_1") (pintype "passive"))
    )
    (net (code "38") (name "/I2C2_SDA") (class "Default")
      (node (ref "R8") (pin "1") (pinfunction "1_1") (pintype "passive"))
    )
    (net (code "39") (name "/I2C3_SCL") (class "Default")
      (node (ref "U1") (pin "B8") (pinfunction "SCL_B8") (pintype "passive"))
    )
    (net (code "40") (name "/I2C3_SDA") (class "Default")
      (node (ref "U1") (pin "B7") (pinfunction "SDA_B7") (pintype "passive"))
    )
    (net (code "41") (name "/POK_1V8") (class "Default")
      (node (ref "R5") (pin "1") (pinfunction "1_1") (pintype "passive"))
      (node (ref "R81") (pin "1") (pinfunction "1_1") (pintype "passive"))
      (node (ref "U2") (pin "3") (pinfunction "PG_3") (pintype "passive"))
    )
    (net (code "42") (name "/POK_3V3") (class "Default")
      (node (ref "U2") (pin "5") (pinfunction "EN_5") (pintype "passive"))
    )
    (net (code "43") (name "/POKn") (class "Default")
      (node (ref "R5") (pin "2") (pinfunction "2_2") (pintype "passive"))
    )
    (net (code "44") (name "/SS_+1V8") (class "Default")
      (node (ref "C59") (pin "1") (pinfunction "1_1") (pintype "passive"))
      (node (ref "U2") (pin "7") (pinfunction "SS_7") (pintype "passive"))
    )
    (net (code "45") (name "/VID_IN_CSI0_D0") (class "Default")
      (node (ref "R1") (pin "2") (pinfunction "2_2") (pintype "passive"))
      (node (ref "TP2") (pin "1") (pinfunction "1_1") (pintype "passive"))
    )
    (net (code "46") (name "/VID_IN_CSI0_D1") (class "Default")
      (node (ref "R2") (pin "2") (pinfunction "2_2") (pintype "passive"))
      (node (ref "TP3") (pin "1") (pinfunction "1_1") (pintype "passive"))
    )
    (net (code "47") (name "/VID_IN_CSI0_D2") (class "Default")
      (node (ref "U1") (pin "F10") (pinfunction "P0_F10") (pintype "passive"))
    )
    (net (code "48") (name "/VID_IN_CSI0_D3") (class "Default")
      (node (ref "U1") (pin "G9") (pinfunction "P1_G9") (pintype "passive"))
    )
    (net (code "49") (name "/VID_IN_CSI0_D4") (class "Default")
      (node (ref "U1") (pin "G10") (pinfunction "P2_G10") (pintype "passive"))
    )
    (net (code "50") (name "/VID_IN_CSI0_D5") (class "Default")
      (node (ref "U1") (pin "H9") (pinfunction "P3_H9") (pintype "passive"))
    )
    (net (code "51") (name "/VID_IN_CSI0_D6") (class "Default")
      (node (ref "U1") (pin "H10") (pinfunction "P4_H10") (pintype "passive"))
    )
    (net (code "52") (name "/VID_IN_CSI0_D7") (class "Default")
      (node (ref "U1") (pin "J9") (pinfunction "P5_J9") (pintype "passive"))
    )
    (net (code "53") (name "/VID_IN_CSI0_D8") (class "Default")
      (node (ref "U1") (pin "K9") (pinfunction "P6_K9") (pintype "passive"))
    )
    (net (code "54") (name "/VID_IN_CSI0_D9") (class "Default")
      (node (ref "U1") (pin "J8") (pinfunction "P7_J8") (pintype "passive"))
    )
    (net (code "55") (name "/VID_IN_CSI0_D10") (class "Default")
      (node (ref "R3") (pin "2") (pinfunction "2_2") (pintype "passive"))
      (node (ref "TP5") (pin "1") (pinfunction "1_1") (pintype "passive"))
    )
    (net (code "56") (name "/VID_IN_CSI0_D11") (class "Default")
      (node (ref "R4") (pin "2") (pinfunction "2_2") (pintype "passive"))
      (node (ref "TP6") (pin "1") (pinfunction "1_1") (pintype "passive"))
    )
    (net (code "57") (name "/VID_IN_CSI0_D12") (class "Default")
      (node (ref "U1") (pin "K8") (pinfunction "P8_K8") (pintype "passive"))
    )
    (net (code "58") (name "/VID_IN_CSI0_D13") (class "Default")
      (node (ref "U1") (pin "J7") (pinfunction "P9_J7") (pintype "passive"))
    )
    (net (code "59") (name "/VID_IN_CSI0_D14") (class "Default")
      (node (ref "U1") (pin "K7") (pinfunction "P10_K7") (pintype "passive"))
    )
    (net (code "60") (name "/VID_IN_CSI0_D15") (class "Default")
      (node (ref "U1") (pin "J6") (pinfunction "P11_J6") (pintype "passive"))
    )
    (net (code "61") (name "/VID_IN_CSI0_D16") (class "Default")
      (node (ref "U1") (pin "K6") (pinfunction "P12_K6") (pintype "passive"))
    )
    (net (code "62") (name "/VID_IN_CSI0_D17") (class "Default")
      (node (ref "U1") (pin "J5") (pinfunction "P13_J5") (pintype "passive"))
    )
    (net (code "63") (name "/VID_IN_CSI0_D18") (class "Default")
      (node (ref "U1") (pin "K5") (pinfunction "P14_K5") (pintype "passive"))
    )
    (net (code "64") (name "/VID_IN_CSI0_D19") (class "Default")
      (node (ref "U1") (pin "J4") (pinfunction "P15_J4") (pintype "passive"))
    )
    (net (code "65") (name "/VID_IN_CSI0_DE") (class "Default")
      (node (ref "U1") (pin "E10") (pinfunction "DE_E10") (pintype "passive"))
    )
    (net (code "66") (name "/VID_IN_CSI0_HS") (class "Default")
      (node (ref "U1") (pin "F9") (pinfunction "HS_F9") (pintype "passive"))
    )
    (net (code "67") (name "/VID_IN_CSI0_INT") (class "Default")
      (node (ref "R109") (pin "1") (pinfunction "1_1") (pintype "passive"))
    )
    (net (code "68") (name "/VID_IN_CSI0_INT_R") (class "Default")
      (node (ref "R109") (pin "2") (pinfunction "2_2") (pintype "passive"))
      (node (ref "U1") (pin "A7") (pinfunction "INT1_A7") (pintype "passive"))
    )
    (net (code "69") (name "/VID_IN_CSI0_PIXCLK") (class "Default")
      (node (ref "R66") (pin "1") (pinfunction "1_1") (pintype "passive"))
    )
    (net (code "70") (name "/VID_IN_CSI0_PIXCLK_R") (class "Default")
      (node (ref "R66") (pin "2") (pinfunction "2_2") (pintype "passive"))
      (node (ref "U1") (pin "K4") (pinfunction "LLC_K4") (pintype "passive"))
    )
    (net (code "71") (name "/VID_IN_CSI0_RSTn") (class "Default")
      (node (ref "U1") (pin "B6") (pinfunction "~{RESET}_B6") (pintype "passive"))
    )
    (net (code "72") (name "/VID_IN_CSI0_VS") (class "Default")
      (node (ref "U1") (pin "E9") (pinfunction "VS_/__FIELD_/__ALSB_E9") (pintype "passive"))
    )
    (net (code "73") (name "GND") (class "Default")
      (node (ref "C177") (pin "1") (pinfunction "1_1") (pintype "passive"))
      (node (ref "C183") (pin "2") (pinfunction "2_2") (pintype "passive"))
      (node (ref "C184") (pin "2") (pinfunction "2_2") (pintype "passive"))
      (node (ref "C185") (pin "2") (pinfunction "2_2") (pintype "passive"))
      (node (ref "C187") (pin "1") (pinfunction "1_1") (pintype "passive"))
      (node (ref "C188") (pin "1") (pinfunction "1_1") (pintype "passive"))
      (node (ref "C190") (pin "1") (pinfunction "1_1") (pintype "passive"))
      (node (ref "C41") (pin "1") (pinfunction "1_1") (pintype "passive"))
      (node (ref "C42") (pin "1") (pinfunction "1_1") (pintype "passive"))
      (node (ref "C43") (pin "1") (pinfunction "1_1") (pintype "passive"))
      (node (ref "C44") (pin "1") (pinfunction "1_1") (pintype "passive"))
      (node (ref "C45") (pin "2") (pinfunction "2_2") (pintype "passive"))
      (node (ref "C46") (pin "2") (pinfunction "2_2") (pintype "passive"))
      (node (ref "C47") (pin "2") (pinfunction "2_2") (pintype "passive"))
      (node (ref "C48") (pin "2") (pinfunction "2_2") (pintype "passive"))
      (node (ref "C49") (pin "2") (pinfunction "2_2") (pintype "passive"))
      (node (ref "C50") (pin "2") (pinfunction "2_2") (pintype "passive"))
      (node (ref "C51") (pin "2") (pinfunction "2_2") (pintype "passive"))
      (node (ref "C52") (pin "1") (pinfunction "1_1") (pintype "passive"))
      (node (ref "C53") (pin "1") (pinfunction "1_1") (pintype "passive"))
      (node (ref "C54") (pin "1") (pinfunction "1_1") (pintype "passive"))
      (node (ref "C55") (pin "1") (pinfunction "1_1") (pintype "passive"))
      (node (ref "C56") (pin "2") (pinfunction "2_2") (pintype "passive"))
      (node (ref "C57") (pin "2") (pinfunction "2_2") (pintype "passive"))
      (node (ref "C58") (pin "2") (pinfunction "2_2") (pintype "passive"))
      (node (ref "C59") (pin "2") (pinfunction "2_2") (pintype "passive"))
      (node (ref "R1") (pin "1") (pinfunction "1_1") (pintype "passive"))
      (node (ref "R2") (pin "1") (pinfunction "1_1") (pintype "passive"))
      (node (ref "R3") (pin "1") (pinfunction "1_1") (pintype "passive"))
      (node (ref "R4") (pin "1") (pinfunction "1_1") (pintype "passive"))
      (node (ref "R83") (pin "1") (pinfunction "1_1") (pintype "passive"))
      (node (ref "U1") (pin "B5") (pinfunction "~{CS}_B5") (pintype "passive"))
      (node (ref "U1") (pin "D4") (pinfunction "GND_1_D4") (pintype "passive"))
      (node (ref "U1") (pin "D5") (pinfunction "GND_2_D5") (pintype "passive"))
      (node (ref "U1") (pin "D6") (pinfunction "GND_3_D6") (pintype "passive"))
      (node (ref "U1") (pin "E4") (pinfunction "GND_4_E4") (pintype "passive"))
      (node (ref "U1") (pin "F4") (pinfunction "GND_5_F4") (pintype "passive"))
      (node (ref "U1") (pin "G4") (pinfunction "GND_6_G4") (pintype "passive"))
      (node (ref "U1") (pin "G5") (pinfunction "GND_7_G5") (pintype "passive"))
      (node (ref "U1") (pin "G6") (pinfunction "GND_8_G6") (pintype "passive"))
      (node (ref "U2") (pin "11") (pinfunction "EPAD_1_11") (pintype "passive"))
      (node (ref "U2") (pin "12") (pinfunction "EPAD_2_12") (pintype "passive"))
      (node (ref "U2") (pin "13") (pinfunction "EPAD_3_13") (pintype "passive"))
      (node (ref "U2") (pin "14") (pinfunction "EPAD_4_14") (pintype "passive"))
      (node (ref "U2") (pin "15") (pinfunction "EPAD_5_15") (pintype "passive"))
      (node (ref "U2") (pin "6") (pinfunction "GND_6") (pintype "passive"))
      (node (ref "Y1") (pin "2") (pinfunction "2_2") (pintype "passive"))
      (node (ref "Y1") (pin "4") (pinfunction "4_4") (pintype "passive"))
    )
    (net (code "74") (name "unconnected-(U1-I2S1-PadC10)") (class "Default")
      (node (ref "U1") (pin "C10") (pinfunction "I2S1_C10") (pintype "passive+no_connect"))
    )
    (net (code "75") (name "unconnected-(U1-I2S2-PadD9)") (class "Default")
      (node (ref "U1") (pin "D9") (pinfunction "I2S2_D9") (pintype "passive+no_connect"))
    )
    (net (code "76") (name "unconnected-(U1-I2S3-PadC9)") (class "Default")
      (node (ref "U1") (pin "C9") (pinfunction "I2S3_C9") (pintype "passive+no_connect"))
    )
    (net (code "77") (name "unconnected-(U1-P16-PadJ3)") (class "Default")
      (node (ref "U1") (pin "J3") (pinfunction "P16_J3") (pintype "passive+no_connect"))
    )
    (net (code "78") (name "unconnected-(U1-P17-PadK3)") (class "Default")
      (node (ref "U1") (pin "K3") (pinfunction "P17_K3") (pintype "passive+no_connect"))
    )
    (net (code "79") (name "unconnected-(U1-P18-PadJ2)") (class "Default")
      (node (ref "U1") (pin "J2") (pinfunction "P18_J2") (pintype "passive+no_connect"))
    )
    (net (code "80") (name "unconnected-(U1-P19-PadK2)") (class "Default")
      (node (ref "U1") (pin "K2") (pinfunction "P19_K2") (pintype "passive+no_connect"))
    )
    (net (code "81") (name "unconnected-(U1-P20-PadK1)") (class "Default")
      (node (ref "U1") (pin "K1") (pinfunction "P20_K1") (pintype "passive+no_connect"))
    )
    (net (code "82") (name "unconnected-(U1-P21-PadJ1)") (class "Default")
      (node (ref "U1") (pin "J1") (pinfunction "P21_J1") (pintype "passive+no_connect"))
    )
    (net (code "83") (name "unconnected-(U1-P22-PadH2)") (class "Default")
      (node (ref "U1") (pin "H2") (pinfunction "P22_H2") (pintype "passive+no_connect"))
    )
    (net (code "84") (name "unconnected-(U1-P23-PadH1)") (class "Default")
      (node (ref "U1") (pin "H1") (pinfunction "P23_H1") (pintype "passive+no_connect"))
    )
  )
)
